# Exp_Board_Slolu.net
KiCad netlist of a schematic drawn in EAGLE
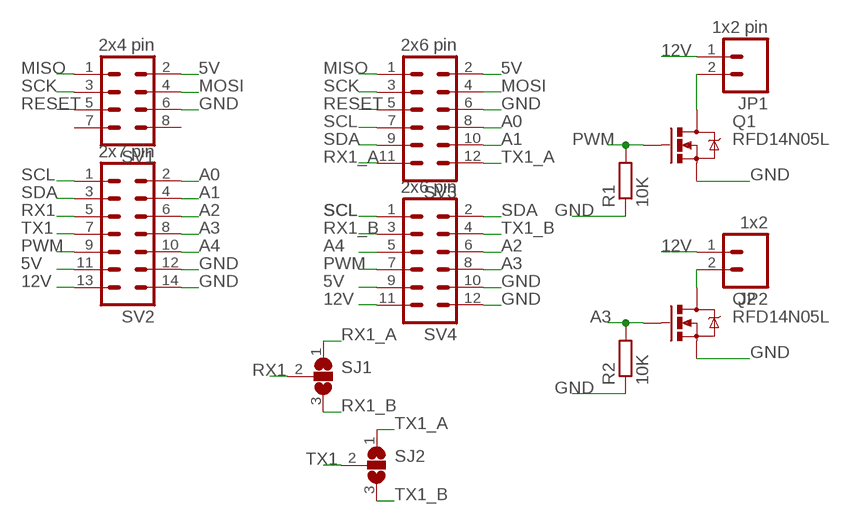
[diagram p0: schematic, sheet 1]

(export (version "E")
  (design (tool "Eeschema 10.0.6"))
  (components
    (comp (ref "JP1")
      (value "1x2 pin")
      (footprint "eagle-import:1X02")
      (libsource (lib "eagle-import") (part "M02PTH"))
    )
    (comp (ref "JP2")
      (value "1x2")
      (footprint "eagle-import:1X02")
      (libsource (lib "eagle-import") (part "M02PTH"))
    )
    (comp (ref "Q1")
      (value "RFD14N05L")
      (footprint "eagle-import:TO220V")
      (libsource (lib "eagle-import") (part "MOSFET-NCHANNELPTH2"))
    )
    (comp (ref "Q2")
      (value "RFD14N05L")
      (footprint "eagle-import:TO220V")
      (libsource (lib "eagle-import") (part "MOSFET-NCHANNELPTH2"))
    )
    (comp (ref "R1")
      (value "10K")
      (footprint "eagle-import:0204_7")
      (libsource (lib "eagle-import") (part "R-EU_0204/7"))
    )
    (comp (ref "R2")
      (value "10K")
      (footprint "eagle-import:0204_7")
      (libsource (lib "eagle-import") (part "R-EU_0204/7"))
    )
    (comp (ref "SJ1")
      (value "SJ2W")
      (footprint "eagle-import:SJ_2")
      (libsource (lib "eagle-import") (part "SJ2W"))
    )
    (comp (ref "SJ2")
      (value "SJ2W")
      (footprint "eagle-import:SJ_2")
      (libsource (lib "eagle-import") (part "SJ2W"))
    )
    (comp (ref "SV1")
      (value "2x4 pin")
      (footprint "eagle-import:MA04-2")
      (libsource (lib "eagle-import") (part "MA04-2"))
    )
    (comp (ref "SV2")
      (value "2x7 pin")
      (footprint "eagle-import:MA07-2")
      (libsource (lib "eagle-import") (part "MA07-2"))
    )
    (comp (ref "SV3")
      (value "2x6 pin")
      (footprint "eagle-import:MA06-2")
      (libsource (lib "eagle-import") (part "MA06-2"))
    )
    (comp (ref "SV4")
      (value "2x6 pin")
      (footprint "eagle-import:MA06-2")
      (libsource (lib "eagle-import") (part "MA06-2"))
    )
  )
  (nets
    (net (code "1") (name "/5V") (class "Default")
      (node (ref "SV1") (pin "2") (pinfunction "2_2") (pintype "passive"))
      (node (ref "SV2") (pin "11") (pinfunction "11_11") (pintype "passive"))
      (node (ref "SV3") (pin "2") (pinfunction "2_2") (pintype "passive"))
      (node (ref "SV4") (pin "9") (pinfunction "9_9") (pintype "passive"))
    )
    (net (code "2") (name "/12V") (class "Default")
      (node (ref "JP1") (pin "1") (pinfunction "1_1") (pintype "passive"))
      (node (ref "JP2") (pin "1") (pinfunction "1_1") (pintype "passive"))
      (node (ref "SV2") (pin "13") (pinfunction "13_13") (pintype "passive"))
      (node (ref "SV4") (pin "11") (pinfunction "11_11") (pintype "passive"))
    )
    (net (code "3") (name "/A0") (class "Default")
      (node (ref "SV2") (pin "2") (pinfunction "2_2") (pintype "passive"))
      (node (ref "SV3") (pin "8") (pinfunction "8_8") (pintype "passive"))
    )
    (net (code "4") (name "/A1") (class "Default")
      (node (ref "SV2") (pin "4") (pinfunction "4_4") (pintype "passive"))
      (node (ref "SV3") (pin "10") (pinfunction "10_10") (pintype "passive"))
    )
    (net (code "5") (name "/A2") (class "Default")
      (node (ref "SV2") (pin "6") (pinfunction "6_6") (pintype "passive"))
      (node (ref "SV4") (pin "6") (pinfunction "6_6") (pintype "passive"))
    )
    (net (code "6") (name "/A3") (class "Default")
      (node (ref "Q2") (pin "1") (pinfunction "G_1") (pintype "passive"))
      (node (ref "R2") (pin "2") (pinfunction "2_2") (pintype "passive"))
      (node (ref "SV2") (pin "8") (pinfunction "8_8") (pintype "passive"))
      (node (ref "SV4") (pin "8") (pinfunction "8_8") (pintype "passive"))
    )
    (net (code "7") (name "/A4") (class "Default")
      (node (ref "SV2") (pin "10") (pinfunction "10_10") (pintype "passive"))
      (node (ref "SV4") (pin "5") (pinfunction "5_5") (pintype "passive"))
    )
    (net (code "8") (name "/GND") (class "Default")
      (node (ref "Q1") (pin "3") (pinfunction "S_3") (pintype "passive"))
      (node (ref "Q2") (pin "3") (pinfunction "S_3") (pintype "passive"))
      (node (ref "R1") (pin "1") (pinfunction "1_1") (pintype "passive"))
      (node (ref "R2") (pin "1") (pinfunction "1_1") (pintype "passive"))
      (node (ref "SV1") (pin "6") (pinfunction "6_6") (pintype "passive"))
      (node (ref "SV2") (pin "12") (pinfunction "12_12") (pintype "passive"))
      (node (ref "SV2") (pin "14") (pinfunction "14_14") (pintype "passive"))
      (node (ref "SV3") (pin "6") (pinfunction "6_6") (pintype "passive"))
      (node (ref "SV4") (pin "10") (pinfunction "10_10") (pintype "passive"))
      (node (ref "SV4") (pin "12") (pinfunction "12_12") (pintype "passive"))
    )
    (net (code "9") (name "/MISO") (class "Default")
      (node (ref "SV1") (pin "1") (pinfunction "1_1") (pintype "passive"))
      (node (ref "SV3") (pin "1") (pinfunction "1_1") (pintype "passive"))
    )
    (net (code "10") (name "/MOSI") (class "Default")
      (node (ref "SV1") (pin "4") (pinfunction "4_4") (pintype "passive"))
      (node (ref "SV3") (pin "4") (pinfunction "4_4") (pintype "passive"))
    )
    (net (code "11") (name "/PWM") (class "Default")
      (node (ref "Q1") (pin "1") (pinfunction "G_1") (pintype "passive"))
      (node (ref "R1") (pin "2") (pinfunction "2_2") (pintype "passive"))
      (node (ref "SV2") (pin "9") (pinfunction "9_9") (pintype "passive"))
      (node (ref "SV4") (pin "7") (pinfunction "7_7") (pintype "passive"))
    )
    (net (code "12") (name "/RESET") (class "Default")
      (node (ref "SV1") (pin "5") (pinfunction "5_5") (pintype "passive"))
      (node (ref "SV3") (pin "5") (pinfunction "5_5") (pintype "passive"))
    )
    (net (code "13") (name "/RX1") (class "Default")
      (node (ref "SJ1") (pin "2") (pinfunction "2_2") (pintype "passive"))
      (node (ref "SV2") (pin "5") (pinfunction "5_5") (pintype "passive"))
    )
    (net (code "14") (name "/RX1_A") (class "Default")
      (node (ref "SJ1") (pin "1") (pinfunction "1_1") (pintype "passive"))
      (node (ref "SV3") (pin "11") (pinfunction "11_11") (pintype "passive"))
    )
    (net (code "15") (name "/RX1_B") (class "Default")
      (node (ref "SJ1") (pin "3") (pinfunction "3_3") (pintype "passive"))
      (node (ref "SV4") (pin "3") (pinfunction "3_3") (pintype "passive"))
    )
    (net (code "16") (name "/SCK") (class "Default")
      (node (ref "SV1") (pin "3") (pinfunction "3_3") (pintype "passive"))
      (node (ref "SV3") (pin "3") (pinfunction "3_3") (pintype "passive"))
    )
    (net (code "17") (name "/SCL") (class "Default")
      (node (ref "SV2") (pin "1") (pinfunction "1_1") (pintype "passive"))
      (node (ref "SV3") (pin "7") (pinfunction "7_7") (pintype "passive"))
      (node (ref "SV4") (pin "1") (pinfunction "1_1") (pintype "passive"))
    )
    (net (code "18") (name "/SDA") (class "Default")
      (node (ref "SV2") (pin "3") (pinfunction "3_3") (pintype "passive"))
      (node (ref "SV3") (pin "9") (pinfunction "9_9") (pintype "passive"))
      (node (ref "SV4") (pin "2") (pinfunction "2_2") (pintype "passive"))
    )
    (net (code "19") (name "/TX1") (class "Default")
      (node (ref "SJ2") (pin "2") (pinfunction "2_2") (pintype "passive"))
      (node (ref "SV2") (pin "7") (pinfunction "7_7") (pintype "passive"))
    )
    (net (code "20") (name "/TX1_A") (class "Default")
      (node (ref "SJ2") (pin "1") (pinfunction "1_1") (pintype "passive"))
      (node (ref "SV3") (pin "12") (pinfunction "12_12") (pintype "passive"))
    )
    (net (code "21") (name "/TX1_B") (class "Default")
      (node (ref "SJ2") (pin "3") (pinfunction "3_3") (pintype "passive"))
      (node (ref "SV4") (pin "4") (pinfunction "4_4") (pintype "passive"))
    )
    (net (code "22") (name "Net-(Q1-D)") (class "Default")
      (node (ref "JP1") (pin "2") (pinfunction "2_2") (pintype "passive"))
      (node (ref "Q1") (pin "2") (pinfunction "D_2") (pintype "passive"))
    )
    (net (code "23") (name "Net-(Q2-D)") (class "Default")
      (node (ref "JP2") (pin "2") (pinfunction "2_2") (pintype "passive"))
      (node (ref "Q2") (pin "2") (pinfunction "D_2") (pintype "passive"))
    )
    (net (code "24") (name "unconnected-(SV1-Pad7)") (class "Default")
      (node (ref "SV1") (pin "7") (pinfunction "7_7") (pintype "passive"))
    )
    (net (code "25") (name "unconnected-(SV1-Pad8)") (class "Default")
      (node (ref "SV1") (pin "8") (pinfunction "8_8") (pintype "passive"))
    )
  )
)
